# sequenceGameRev1-0.net
KiCad netlist of a schematic drawn in EAGLE
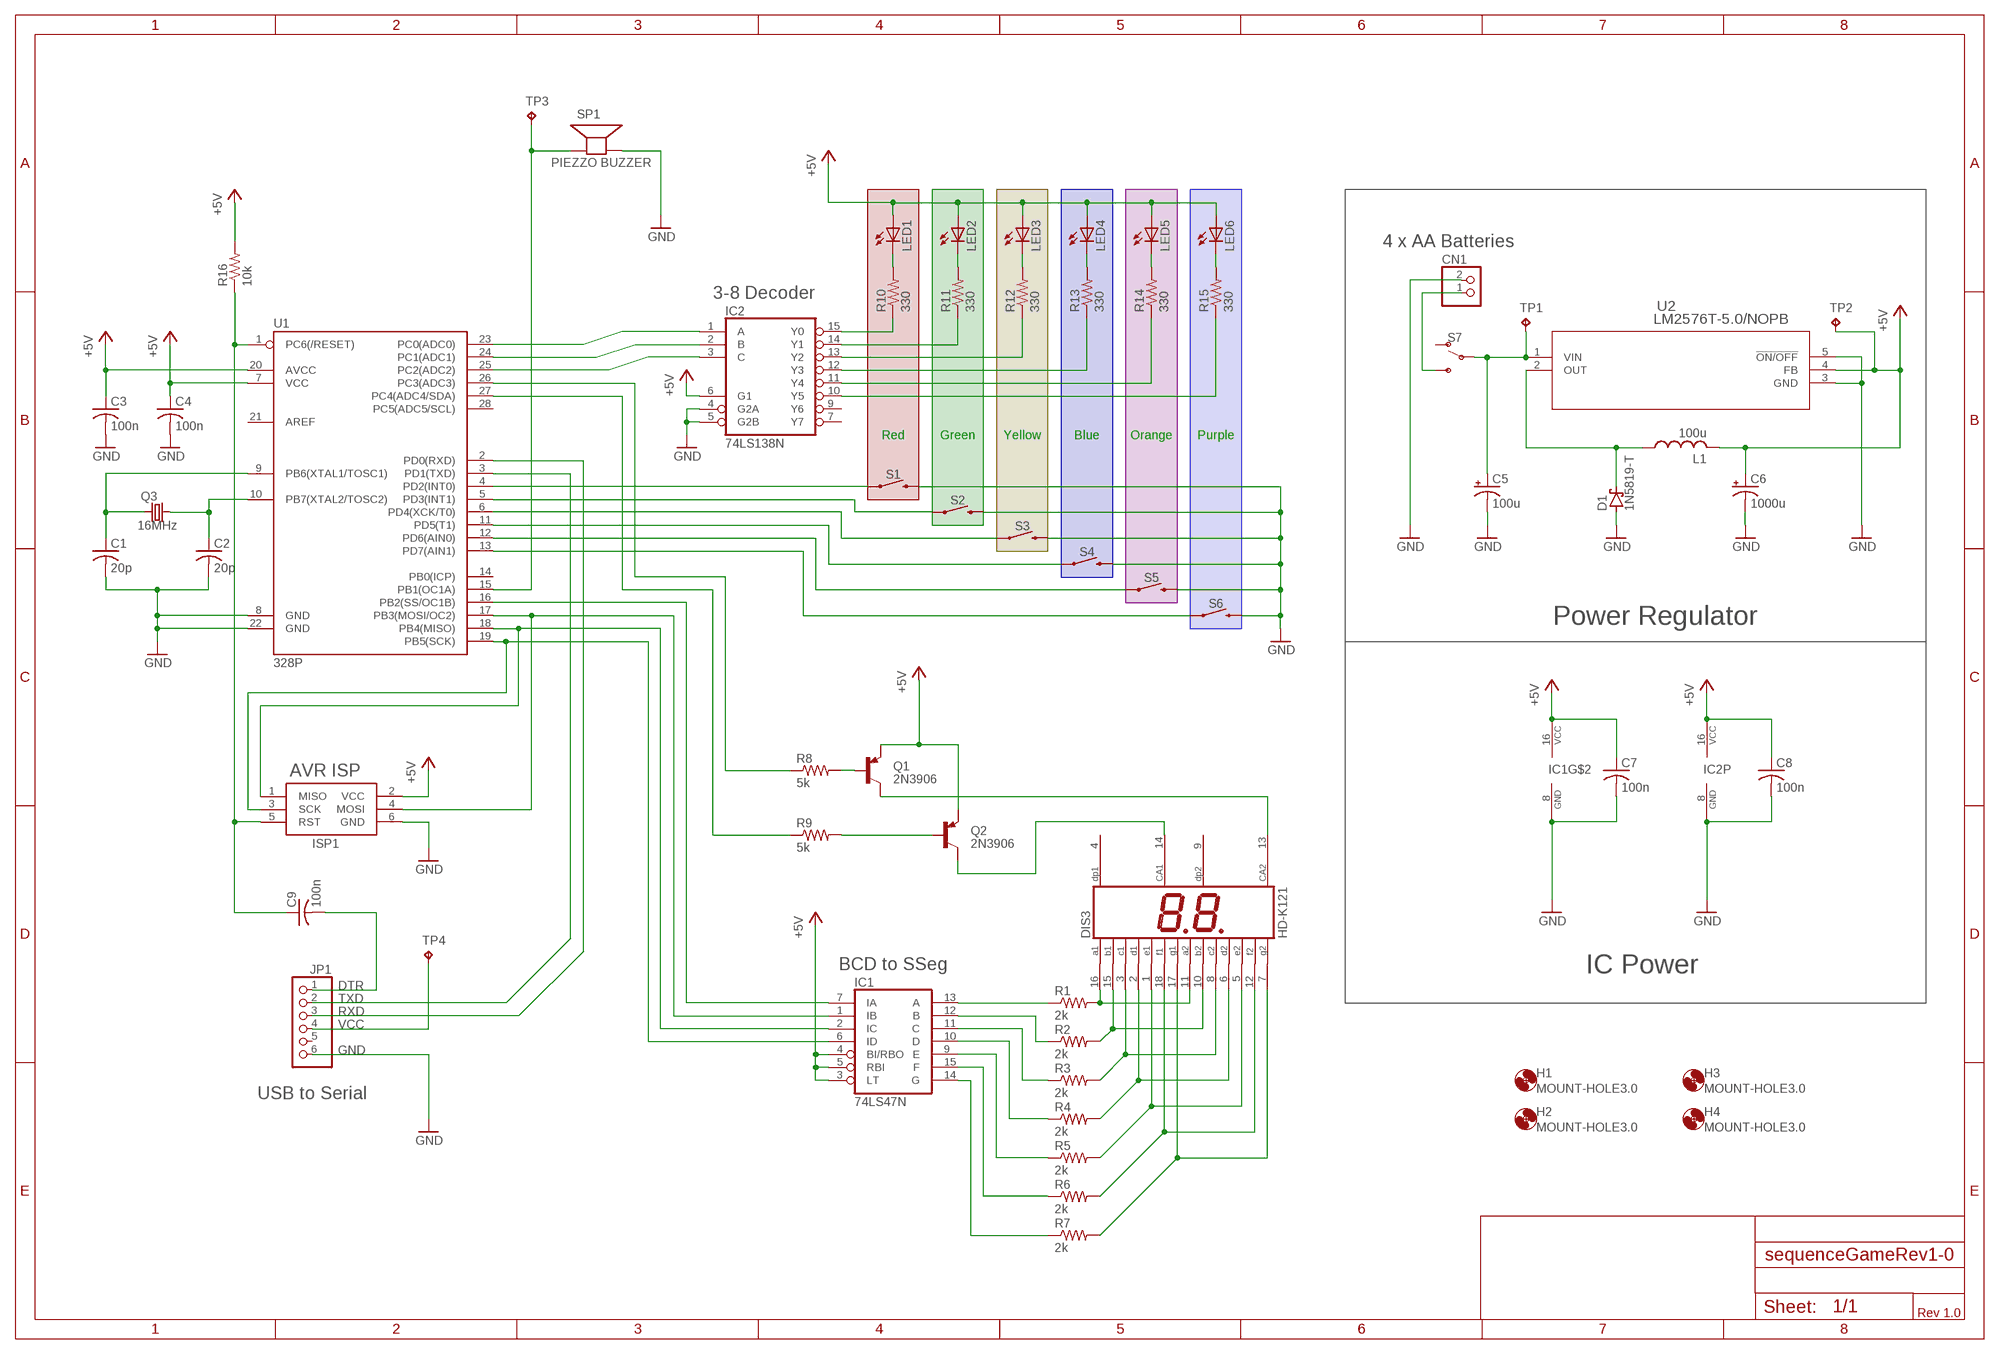
[diagram p0: schematic, sheet 1]

(export (version "E")
  (design (tool "Eeschema 10.0.6"))
  (components
    (comp (ref "C1")
      (value "20p")
      (footprint "eagle-import:C050-025X075")
      (libsource (lib "eagle-import") (part "C-US050-025X075"))
    )
    (comp (ref "C2")
      (value "20p")
      (footprint "eagle-import:C050-025X075")
      (libsource (lib "eagle-import") (part "C-US050-025X075"))
    )
    (comp (ref "C3")
      (value "100n")
      (footprint "eagle-import:C050-025X075")
      (libsource (lib "eagle-import") (part "C-US050-025X075"))
    )
    (comp (ref "C4")
      (value "100n")
      (footprint "eagle-import:C050-025X075")
      (libsource (lib "eagle-import") (part "C-US050-025X075"))
    )
    (comp (ref "C5")
      (value "100u")
      (footprint "eagle-import:E2,5-5")
      (libsource (lib "eagle-import") (part "CPOL-USE2.5-5"))
    )
    (comp (ref "C6")
      (value "1000u")
      (footprint "eagle-import:E5-10,5")
      (libsource (lib "eagle-import") (part "CPOL-USE5-10.5"))
    )
    (comp (ref "C7")
      (value "100n")
      (footprint "eagle-import:C050-025X075")
      (libsource (lib "eagle-import") (part "C-US050-025X075"))
    )
    (comp (ref "C8")
      (value "100n")
      (footprint "eagle-import:C050-025X075")
      (libsource (lib "eagle-import") (part "C-US050-025X075"))
    )
    (comp (ref "C9")
      (value "100n")
      (footprint "eagle-import:C050-025X075")
      (libsource (lib "eagle-import") (part "C-US050-025X075"))
    )
    (comp (ref "CN1")
      (value "JST_2PIN-THM")
      (footprint "eagle-import:JST-PH-2-THM")
      (libsource (lib "eagle-import") (part "JST_2PIN-THM"))
    )
    (comp (ref "D1")
      (value "1N5819-T")
      (footprint "eagle-import:DO41-7.6")
      (libsource (lib "eagle-import") (part "1N5819-T"))
    )
    (comp (ref "DIS3")
      (value "HD-K121")
      (footprint "eagle-import:HDSP-R")
      (libsource (lib "eagle-import") (part "HD-K121"))
    )
    (comp (ref "H1")
      (value "MOUNT-HOLE3.0")
      (footprint "eagle-import:3,0")
      (libsource (lib "eagle-import") (part "MOUNT-HOLE3.0"))
    )
    (comp (ref "H2")
      (value "MOUNT-HOLE3.0")
      (footprint "eagle-import:3,0")
      (libsource (lib "eagle-import") (part "MOUNT-HOLE3.0"))
    )
    (comp (ref "H3")
      (value "MOUNT-HOLE3.0")
      (footprint "eagle-import:3,0")
      (libsource (lib "eagle-import") (part "MOUNT-HOLE3.0"))
    )
    (comp (ref "H4")
      (value "MOUNT-HOLE3.0")
      (footprint "eagle-import:3,0")
      (libsource (lib "eagle-import") (part "MOUNT-HOLE3.0"))
    )
    (comp (ref "IC1")
      (value "74LS47N")
      (footprint "eagle-import:DIL16")
      (libsource (lib "eagle-import") (part "7447NLS"))
    )
    (comp (ref "IC2")
      (value "74LS138N")
      (footprint "eagle-import:DIL16")
      (libsource (lib "eagle-import") (part "74138NLS"))
    )
    (comp (ref "ISP1")
      (value "AVRISP-6")
      (footprint "eagle-import:AVRISP")
      (libsource (lib "eagle-import") (part "AVRISP-6"))
    )
    (comp (ref "JP1")
      (value "PINHD-1X6")
      (footprint "eagle-import:1X06")
      (libsource (lib "eagle-import") (part "PINHD-1X6"))
    )
    (comp (ref "L1")
      (value "100u")
      (footprint "eagle-import:0207_10")
      (libsource (lib "eagle-import") (part "L-US0207/10"))
    )
    (comp (ref "LED1")
      (value "LED5MM")
      (footprint "eagle-import:LED5MM")
      (libsource (lib "eagle-import") (part "LED5MM"))
    )
    (comp (ref "LED2")
      (value "LED5MM")
      (footprint "eagle-import:LED5MM")
      (libsource (lib "eagle-import") (part "LED5MM"))
    )
    (comp (ref "LED3")
      (value "LED5MM")
      (footprint "eagle-import:LED5MM")
      (libsource (lib "eagle-import") (part "LED5MM"))
    )
    (comp (ref "LED4")
      (value "LED5MM")
      (footprint "eagle-import:LED5MM")
      (libsource (lib "eagle-import") (part "LED5MM"))
    )
    (comp (ref "LED5")
      (value "LED5MM")
      (footprint "eagle-import:LED5MM")
      (libsource (lib "eagle-import") (part "LED5MM"))
    )
    (comp (ref "LED6")
      (value "LED5MM")
      (footprint "eagle-import:LED5MM")
      (libsource (lib "eagle-import") (part "LED5MM"))
    )
    (comp (ref "Q1")
      (value "2N3906")
      (footprint "eagle-import:TO92")
      (libsource (lib "eagle-import") (part "2N3906"))
    )
    (comp (ref "Q2")
      (value "2N3906")
      (footprint "eagle-import:TO92")
      (libsource (lib "eagle-import") (part "2N3906"))
    )
    (comp (ref "Q3")
      (value "16MHz")
      (footprint "eagle-import:HC49_S")
      (libsource (lib "eagle-import") (part "CRYSTALHC49S"))
    )
    (comp (ref "R1")
      (value "2k")
      (footprint "eagle-import:0207_10")
      (libsource (lib "eagle-import") (part "R-US_0207/10"))
    )
    (comp (ref "R2")
      (value "2k")
      (footprint "eagle-import:0207_10")
      (libsource (lib "eagle-import") (part "R-US_0207/10"))
    )
    (comp (ref "R3")
      (value "2k")
      (footprint "eagle-import:0207_10")
      (libsource (lib "eagle-import") (part "R-US_0207/10"))
    )
    (comp (ref "R4")
      (value "2k")
      (footprint "eagle-import:0207_10")
      (libsource (lib "eagle-import") (part "R-US_0207/10"))
    )
    (comp (ref "R5")
      (value "2k")
      (footprint "eagle-import:0207_10")
      (libsource (lib "eagle-import") (part "R-US_0207/10"))
    )
    (comp (ref "R6")
      (value "2k")
      (footprint "eagle-import:0207_10")
      (libsource (lib "eagle-import") (part "R-US_0207/10"))
    )
    (comp (ref "R7")
      (value "2k")
      (footprint "eagle-import:0207_10")
      (libsource (lib "eagle-import") (part "R-US_0207/10"))
    )
    (comp (ref "R8")
      (value "5k")
      (footprint "eagle-import:0207_10")
      (libsource (lib "eagle-import") (part "R-US_0207/10"))
    )
    (comp (ref "R9")
      (value "5k")
      (footprint "eagle-import:0207_10")
      (libsource (lib "eagle-import") (part "R-US_0207/10"))
    )
    (comp (ref "R10")
      (value "330")
      (footprint "eagle-import:0207_10")
      (libsource (lib "eagle-import") (part "R-US_0207/10"))
    )
    (comp (ref "R11")
      (value "330")
      (footprint "eagle-import:0207_10")
      (libsource (lib "eagle-import") (part "R-US_0207/10"))
    )
    (comp (ref "R12")
      (value "330")
      (footprint "eagle-import:0207_10")
      (libsource (lib "eagle-import") (part "R-US_0207/10"))
    )
    (comp (ref "R13")
      (value "330")
      (footprint "eagle-import:0207_10")
      (libsource (lib "eagle-import") (part "R-US_0207/10"))
    )
    (comp (ref "R14")
      (value "330")
      (footprint "eagle-import:0207_10")
      (libsource (lib "eagle-import") (part "R-US_0207/10"))
    )
    (comp (ref "R15")
      (value "330")
      (footprint "eagle-import:0207_10")
      (libsource (lib "eagle-import") (part "R-US_0207/10"))
    )
    (comp (ref "R16")
      (value "10k")
      (footprint "eagle-import:0207_10")
      (libsource (lib "eagle-import") (part "R-US_0207/10"))
    )
    (comp (ref "S1")
      (value "MOMENTARY-SWITCH-SPST-PTH-6.0MM")
      (footprint "eagle-import:TACTILE_SWITCH_PTH_6.0MM")
      (libsource (lib "eagle-import") (part "MOMENTARY-SWITCH-SPST-PTH-6.0MM"))
    )
    (comp (ref "S2")
      (value "MOMENTARY-SWITCH-SPST-PTH-6.0MM")
      (footprint "eagle-import:TACTILE_SWITCH_PTH_6.0MM")
      (libsource (lib "eagle-import") (part "MOMENTARY-SWITCH-SPST-PTH-6.0MM"))
    )
    (comp (ref "S3")
      (value "MOMENTARY-SWITCH-SPST-PTH-6.0MM")
      (footprint "eagle-import:TACTILE_SWITCH_PTH_6.0MM")
      (libsource (lib "eagle-import") (part "MOMENTARY-SWITCH-SPST-PTH-6.0MM"))
    )
    (comp (ref "S4")
      (value "MOMENTARY-SWITCH-SPST-PTH-6.0MM")
      (footprint "eagle-import:TACTILE_SWITCH_PTH_6.0MM")
      (libsource (lib "eagle-import") (part "MOMENTARY-SWITCH-SPST-PTH-6.0MM"))
    )
    (comp (ref "S5")
      (value "MOMENTARY-SWITCH-SPST-PTH-6.0MM")
      (footprint "eagle-import:TACTILE_SWITCH_PTH_6.0MM")
      (libsource (lib "eagle-import") (part "MOMENTARY-SWITCH-SPST-PTH-6.0MM"))
    )
    (comp (ref "S6")
      (value "MOMENTARY-SWITCH-SPST-PTH-6.0MM")
      (footprint "eagle-import:TACTILE_SWITCH_PTH_6.0MM")
      (libsource (lib "eagle-import") (part "MOMENTARY-SWITCH-SPST-PTH-6.0MM"))
    )
    (comp (ref "S7")
      (value "SWITCH-SPDT-PTH-11.6X4.0MM")
      (footprint "eagle-import:SWITCH_SPDT_PTH_11.6X4.0MM")
      (libsource (lib "eagle-import") (part "SWITCH-SPDT-PTH-11.6X4.0MM"))
    )
    (comp (ref "SP1")
      (value "PIEZZO BUZZER")
      (footprint "eagle-import:AL60P")
      (libsource (lib "eagle-import") (part "SPEAKER/AL60P"))
    )
    (comp (ref "TP1")
      (value "TPB1,27")
      (footprint "eagle-import:B1,27")
      (libsource (lib "eagle-import") (part "TPB1,27"))
    )
    (comp (ref "TP2")
      (value "TPB1,27")
      (footprint "eagle-import:B1,27")
      (libsource (lib "eagle-import") (part "TPB1,27"))
    )
    (comp (ref "TP3")
      (value "TPB1,27")
      (footprint "eagle-import:B1,27")
      (libsource (lib "eagle-import") (part "TPB1,27"))
    )
    (comp (ref "TP4")
      (value "TPB1,27")
      (footprint "eagle-import:B1,27")
      (libsource (lib "eagle-import") (part "TPB1,27"))
    )
    (comp (ref "U1")
      (value "328P")
      (footprint "eagle-import:DIP28")
      (libsource (lib "eagle-import") (part "ATMEGA328P_PDIP"))
    )
    (comp (ref "U2")
      (value "LM2576T-5.0/NOPB")
      (footprint "eagle-import:T05A_TEX")
      (fields (field (name "COPYRIGHT") "Copyright (C) 2018 Accelerated Designs. All rights reserved"))
      (libsource (lib "eagle-import") (part "LM2576T-5.0/NOPB"))
    )
  )
  (nets
    (net (code "1") (name "+5V") (class "Default")
      (node (ref "C3") (pin "1") (pinfunction "1_1") (pintype "passive"))
      (node (ref "C4") (pin "1") (pinfunction "1_1") (pintype "passive"))
      (node (ref "C6") (pin "+") (pinfunction "+_+") (pintype "passive"))
      (node (ref "C7") (pin "1") (pinfunction "1_1") (pintype "passive"))
      (node (ref "C8") (pin "1") (pinfunction "1_1") (pintype "passive"))
      (node (ref "IC1") (pin "16") (pinfunction "VCC_16") (pintype "power_in"))
      (node (ref "IC1") (pin "3") (pinfunction "LT_3") (pintype "input"))
      (node (ref "IC1") (pin "4") (pinfunction "BI/RBO_4") (pintype "input"))
      (node (ref "IC1") (pin "5") (pinfunction "RBI_5") (pintype "input"))
      (node (ref "IC2") (pin "16") (pinfunction "VCC_16") (pintype "power_in"))
      (node (ref "IC2") (pin "6") (pinfunction "G1_6") (pintype "input"))
      (node (ref "ISP1") (pin "2") (pinfunction "VCC_2") (pintype "power_in"))
      (node (ref "L1") (pin "2") (pinfunction "2_2") (pintype "passive"))
      (node (ref "LED1") (pin "A") (pinfunction "A_A") (pintype "passive"))
      (node (ref "LED2") (pin "A") (pinfunction "A_A") (pintype "passive"))
      (node (ref "LED3") (pin "A") (pinfunction "A_A") (pintype "passive"))
      (node (ref "LED4") (pin "A") (pinfunction "A_A") (pintype "passive"))
      (node (ref "LED5") (pin "A") (pinfunction "A_A") (pintype "passive"))
      (node (ref "LED6") (pin "A") (pinfunction "A_A") (pintype "passive"))
      (node (ref "Q1") (pin "3") (pinfunction "E_3") (pintype "passive"))
      (node (ref "Q2") (pin "3") (pinfunction "E_3") (pintype "passive"))
      (node (ref "R16") (pin "2") (pinfunction "2_2") (pintype "passive"))
      (node (ref "TP2") (pin "TP") (pinfunction "TP_TP") (pintype "input"))
      (node (ref "U1") (pin "20") (pinfunction "AVCC_20") (pintype "bidirectional"))
      (node (ref "U1") (pin "7") (pinfunction "VCC_7") (pintype "bidirectional"))
      (node (ref "U2") (pin "4") (pinfunction "FB_4") (pintype "input"))
    )
    (net (code "2") (name "/DTR") (class "Default")
      (node (ref "C9") (pin "2") (pinfunction "2_2") (pintype "passive"))
      (node (ref "JP1") (pin "1") (pinfunction "1_1") (pintype "passive"))
    )
    (net (code "3") (name "/RXD") (class "Default")
      (node (ref "JP1") (pin "3") (pinfunction "3_3") (pintype "passive"))
      (node (ref "U1") (pin "2") (pinfunction "PD0(RXD)_2") (pintype "bidirectional"))
    )
    (net (code "4") (name "/TXD") (class "Default")
      (node (ref "JP1") (pin "2") (pinfunction "2_2") (pintype "passive"))
      (node (ref "U1") (pin "3") (pinfunction "PD1(TXD)_3") (pintype "bidirectional"))
    )
    (net (code "5") (name "/VCC") (class "Default")
      (node (ref "JP1") (pin "4") (pinfunction "4_4") (pintype "passive"))
      (node (ref "TP4") (pin "TP") (pinfunction "TP_TP") (pintype "input"))
    )
    (net (code "6") (name "GND") (class "Default")
      (node (ref "C1") (pin "2") (pinfunction "2_2") (pintype "passive"))
      (node (ref "C2") (pin "2") (pinfunction "2_2") (pintype "passive"))
      (node (ref "C3") (pin "2") (pinfunction "2_2") (pintype "passive"))
      (node (ref "C4") (pin "2") (pinfunction "2_2") (pintype "passive"))
      (node (ref "C5") (pin "-") (pinfunction "-_-") (pintype "passive"))
      (node (ref "C6") (pin "-") (pinfunction "-_-") (pintype "passive"))
      (node (ref "C7") (pin "2") (pinfunction "2_2") (pintype "passive"))
      (node (ref "C8") (pin "2") (pinfunction "2_2") (pintype "passive"))
      (node (ref "CN1") (pin "2") (pinfunction "1_2") (pintype "passive"))
      (node (ref "D1") (pin "A") (pinfunction "A_A") (pintype "passive"))
      (node (ref "IC1") (pin "8") (pinfunction "GND_8") (pintype "power_in"))
      (node (ref "IC2") (pin "4") (pinfunction "G2A_4") (pintype "input"))
      (node (ref "IC2") (pin "5") (pinfunction "G2B_5") (pintype "input"))
      (node (ref "IC2") (pin "8") (pinfunction "GND_8") (pintype "power_in"))
      (node (ref "ISP1") (pin "6") (pinfunction "GND_6") (pintype "power_in"))
      (node (ref "JP1") (pin "6") (pinfunction "6_6") (pintype "passive"))
      (node (ref "S1") (pin "3") (pinfunction "2_3") (pintype "passive"))
      (node (ref "S2") (pin "3") (pinfunction "2_3") (pintype "passive"))
      (node (ref "S3") (pin "3") (pinfunction "2_3") (pintype "passive"))
      (node (ref "S4") (pin "3") (pinfunction "2_3") (pintype "passive"))
      (node (ref "S5") (pin "3") (pinfunction "2_3") (pintype "passive"))
      (node (ref "S6") (pin "3") (pinfunction "2_3") (pintype "passive"))
      (node (ref "SP1") (pin "2") (pinfunction "-_2") (pintype "passive"))
      (node (ref "U1") (pin "22") (pinfunction "GND_22") (pintype "bidirectional"))
      (node (ref "U1") (pin "8") (pinfunction "GND_8") (pintype "bidirectional"))
      (node (ref "U2") (pin "3") (pinfunction "GND_3") (pintype "power_in"))
      (node (ref "U2") (pin "5") (pinfunction "~{ON/OFF}_5") (pintype "input"))
    )
    (net (code "7") (name "Net-(CN1-2)") (class "Default")
      (node (ref "CN1") (pin "1") (pinfunction "2_1") (pintype "passive"))
      (node (ref "S7") (pin "3") (pinfunction "S_3") (pintype "passive"))
    )
    (net (code "8") (name "Net-(DIS3-A1)") (class "Default")
      (node (ref "DIS3") (pin "11") (pinfunction "A2_11") (pintype "passive"))
      (node (ref "DIS3") (pin "16") (pinfunction "A1_16") (pintype "passive"))
      (node (ref "R1") (pin "2") (pinfunction "2_2") (pintype "passive"))
    )
    (net (code "9") (name "Net-(DIS3-B1)") (class "Default")
      (node (ref "DIS3") (pin "10") (pinfunction "B2_10") (pintype "passive"))
      (node (ref "DIS3") (pin "15") (pinfunction "B1_15") (pintype "passive"))
      (node (ref "R2") (pin "2") (pinfunction "2_2") (pintype "passive"))
    )
    (net (code "10") (name "Net-(DIS3-C1)") (class "Default")
      (node (ref "DIS3") (pin "3") (pinfunction "C1_3") (pintype "passive"))
      (node (ref "DIS3") (pin "8") (pinfunction "C2_8") (pintype "passive"))
      (node (ref "R3") (pin "2") (pinfunction "2_2") (pintype "passive"))
    )
    (net (code "11") (name "Net-(DIS3-CA1)") (class "Default")
      (node (ref "DIS3") (pin "14") (pinfunction "CA1_14") (pintype "passive"))
      (node (ref "Q2") (pin "1") (pinfunction "C_1") (pintype "passive"))
    )
    (net (code "12") (name "Net-(DIS3-CA2)") (class "Default")
      (node (ref "DIS3") (pin "13") (pinfunction "CA2_13") (pintype "passive"))
      (node (ref "Q1") (pin "1") (pinfunction "C_1") (pintype "passive"))
    )
    (net (code "13") (name "Net-(DIS3-D1)") (class "Default")
      (node (ref "DIS3") (pin "2") (pinfunction "D1_2") (pintype "passive"))
      (node (ref "DIS3") (pin "6") (pinfunction "D2_6") (pintype "passive"))
      (node (ref "R4") (pin "2") (pinfunction "2_2") (pintype "passive"))
    )
    (net (code "14") (name "Net-(DIS3-E1)") (class "Default")
      (node (ref "DIS3") (pin "1") (pinfunction "E1_1") (pintype "passive"))
      (node (ref "DIS3") (pin "5") (pinfunction "E2_5") (pintype "passive"))
      (node (ref "R5") (pin "2") (pinfunction "2_2") (pintype "passive"))
    )
    (net (code "15") (name "Net-(DIS3-F1)") (class "Default")
      (node (ref "DIS3") (pin "12") (pinfunction "F2_12") (pintype "passive"))
      (node (ref "DIS3") (pin "18") (pinfunction "F1_18") (pintype "passive"))
      (node (ref "R6") (pin "2") (pinfunction "2_2") (pintype "passive"))
    )
    (net (code "16") (name "Net-(DIS3-G1)") (class "Default")
      (node (ref "DIS3") (pin "17") (pinfunction "G1_17") (pintype "passive"))
      (node (ref "DIS3") (pin "7") (pinfunction "G2_7") (pintype "passive"))
      (node (ref "R7") (pin "2") (pinfunction "2_2") (pintype "passive"))
    )
    (net (code "17") (name "Net-(IC1A-A)") (class "Default")
      (node (ref "IC1") (pin "13") (pinfunction "A_13") (pintype "output"))
      (node (ref "R1") (pin "1") (pinfunction "1_1") (pintype "passive"))
    )
    (net (code "18") (name "Net-(IC1A-B)") (class "Default")
      (node (ref "IC1") (pin "12") (pinfunction "B_12") (pintype "output"))
      (node (ref "R2") (pin "1") (pinfunction "1_1") (pintype "passive"))
    )
    (net (code "19") (name "Net-(IC1A-C)") (class "Default")
      (node (ref "IC1") (pin "11") (pinfunction "C_11") (pintype "output"))
      (node (ref "R3") (pin "1") (pinfunction "1_1") (pintype "passive"))
    )
    (net (code "20") (name "Net-(IC1A-D)") (class "Default")
      (node (ref "IC1") (pin "10") (pinfunction "D_10") (pintype "output"))
      (node (ref "R4") (pin "1") (pinfunction "1_1") (pintype "passive"))
    )
    (net (code "21") (name "Net-(IC1A-E)") (class "Default")
      (node (ref "IC1") (pin "9") (pinfunction "E_9") (pintype "output"))
      (node (ref "R5") (pin "1") (pinfunction "1_1") (pintype "passive"))
    )
    (net (code "22") (name "Net-(IC1A-F)") (class "Default")
      (node (ref "IC1") (pin "15") (pinfunction "F_15") (pintype "output"))
      (node (ref "R6") (pin "1") (pinfunction "1_1") (pintype "passive"))
    )
    (net (code "23") (name "Net-(IC1A-G)") (class "Default")
      (node (ref "IC1") (pin "14") (pinfunction "G_14") (pintype "output"))
      (node (ref "R7") (pin "1") (pinfunction "1_1") (pintype "passive"))
    )
    (net (code "24") (name "Net-(IC1A-IA)") (class "Default")
      (node (ref "IC1") (pin "7") (pinfunction "IA_7") (pintype "input"))
      (node (ref "U1") (pin "16") (pinfunction "PB2(SS/OC1B)_16") (pintype "bidirectional"))
    )
    (net (code "25") (name "Net-(IC1A-IB)") (class "Default")
      (node (ref "IC1") (pin "1") (pinfunction "IB_1") (pintype "input"))
      (node (ref "ISP1") (pin "4") (pinfunction "MOSI_4") (pintype "output"))
      (node (ref "U1") (pin "17") (pinfunction "PB3(MOSI/OC2)_17") (pintype "bidirectional"))
    )
    (net (code "26") (name "Net-(IC1A-IC)") (class "Default")
      (node (ref "IC1") (pin "2") (pinfunction "IC_2") (pintype "input"))
      (node (ref "ISP1") (pin "1") (pinfunction "MISO_1") (pintype "input"))
      (node (ref "U1") (pin "18") (pinfunction "PB4(MISO)_18") (pintype "bidirectional"))
    )
    (net (code "27") (name "Net-(IC1A-ID)") (class "Default")
      (node (ref "IC1") (pin "6") (pinfunction "ID_6") (pintype "input"))
      (node (ref "ISP1") (pin "3") (pinfunction "SCK_3") (pintype "output"))
      (node (ref "U1") (pin "19") (pinfunction "PB5(SCK)_19") (pintype "bidirectional"))
    )
    (net (code "28") (name "Net-(IC2A-A)") (class "Default")
      (node (ref "IC2") (pin "1") (pinfunction "A_1") (pintype "input"))
      (node (ref "U1") (pin "23") (pinfunction "PC0(ADC0)_23") (pintype "bidirectional"))
    )
    (net (code "29") (name "Net-(IC2A-B)") (class "Default")
      (node (ref "IC2") (pin "2") (pinfunction "B_2") (pintype "input"))
      (node (ref "U1") (pin "24") (pinfunction "PC1(ADC1)_24") (pintype "bidirectional"))
    )
    (net (code "30") (name "Net-(IC2A-C)") (class "Default")
      (node (ref "IC2") (pin "3") (pinfunction "C_3") (pintype "input"))
      (node (ref "U1") (pin "25") (pinfunction "PC2(ADC2)_25") (pintype "bidirectional"))
    )
    (net (code "31") (name "Net-(IC2A-Y0)") (class "Default")
      (node (ref "IC2") (pin "15") (pinfunction "Y0_15") (pintype "output"))
      (node (ref "R10") (pin "1") (pinfunction "1_1") (pintype "passive"))
    )
    (net (code "32") (name "Net-(IC2A-Y1)") (class "Default")
      (node (ref "IC2") (pin "14") (pinfunction "Y1_14") (pintype "output"))
      (node (ref "R11") (pin "1") (pinfunction "1_1") (pintype "passive"))
    )
    (net (code "33") (name "Net-(IC2A-Y2)") (class "Default")
      (node (ref "IC2") (pin "13") (pinfunction "Y2_13") (pintype "output"))
      (node (ref "R12") (pin "1") (pinfunction "1_1") (pintype "passive"))
    )
    (net (code "34") (name "Net-(IC2A-Y3)") (class "Default")
      (node (ref "IC2") (pin "12") (pinfunction "Y3_12") (pintype "output"))
      (node (ref "R13") (pin "1") (pinfunction "1_1") (pintype "passive"))
    )
    (net (code "35") (name "Net-(IC2A-Y4)") (class "Default")
      (node (ref "IC2") (pin "11") (pinfunction "Y4_11") (pintype "output"))
      (node (ref "R14") (pin "1") (pinfunction "1_1") (pintype "passive"))
    )
    (net (code "36") (name "Net-(IC2A-Y5)") (class "Default")
      (node (ref "IC2") (pin "10") (pinfunction "Y5_10") (pintype "output"))
      (node (ref "R15") (pin "1") (pinfunction "1_1") (pintype "passive"))
    )
    (net (code "37") (name "Net-(ISP1-RST)") (class "Default")
      (node (ref "C9") (pin "1") (pinfunction "1_1") (pintype "passive"))
      (node (ref "ISP1") (pin "5") (pinfunction "RST_5") (pintype "output"))
      (node (ref "R16") (pin "1") (pinfunction "1_1") (pintype "passive"))
      (node (ref "U1") (pin "1") (pinfunction "PC6(/RESET)_1") (pintype "bidirectional"))
    )
    (net (code "38") (name "Net-(LED1-C)") (class "Default")
      (node (ref "LED1") (pin "K") (pinfunction "C_K") (pintype "passive"))
      (node (ref "R10") (pin "2") (pinfunction "2_2") (pintype "passive"))
    )
    (net (code "39") (name "Net-(LED2-C)") (class "Default")
      (node (ref "LED2") (pin "K") (pinfunction "C_K") (pintype "passive"))
      (node (ref "R11") (pin "2") (pinfunction "2_2") (pintype "passive"))
    )
    (net (code "40") (name "Net-(LED3-C)") (class "Default")
      (node (ref "LED3") (pin "K") (pinfunction "C_K") (pintype "passive"))
      (node (ref "R12") (pin "2") (pinfunction "2_2") (pintype "passive"))
    )
    (net (code "41") (name "Net-(LED4-C)") (class "Default")
      (node (ref "LED4") (pin "K") (pinfunction "C_K") (pintype "passive"))
      (node (ref "R13") (pin "2") (pinfunction "2_2") (pintype "passive"))
    )
    (net (code "42") (name "Net-(LED5-C)") (class "Default")
      (node (ref "LED5") (pin "K") (pinfunction "C_K") (pintype "passive"))
      (node (ref "R14") (pin "2") (pinfunction "2_2") (pintype "passive"))
    )
    (net (code "43") (name "Net-(LED6-C)") (class "Default")
      (node (ref "LED6") (pin "K") (pinfunction "C_K") (pintype "passive"))
      (node (ref "R15") (pin "2") (pinfunction "2_2") (pintype "passive"))
    )
    (net (code "44") (name "Net-(Q1-B)") (class "Default")
      (node (ref "Q1") (pin "2") (pinfunction "B_2") (pintype "passive"))
      (node (ref "R8") (pin "2") (pinfunction "2_2") (pintype "passive"))
    )
    (net (code "45") (name "Net-(Q2-B)") (class "Default")
      (node (ref "Q2") (pin "2") (pinfunction "B_2") (pintype "passive"))
      (node (ref "R9") (pin "2") (pinfunction "2_2") (pintype "passive"))
    )
    (net (code "46") (name "Net-(S7-P)") (class "Default")
      (node (ref "C5") (pin "+") (pinfunction "+_+") (pintype "passive"))
      (node (ref "S7") (pin "2") (pinfunction "P_2") (pintype "passive"))
      (node (ref "TP1") (pin "TP") (pinfunction "TP_TP") (pintype "input"))
      (node (ref "U2") (pin "1") (pinfunction "VIN_1") (pintype "power_in"))
    )
    (net (code "47") (name "Net-(SP1-+)") (class "Default")
      (node (ref "SP1") (pin "1") (pinfunction "+_1") (pintype "passive"))
      (node (ref "TP3") (pin "TP") (pinfunction "TP_TP") (pintype "input"))
      (node (ref "U1") (pin "15") (pinfunction "PB1(OC1A)_15") (pintype "bidirectional"))
    )
    (net (code "48") (name "Net-(U1-PB6(XTAL1{slash}TOSC1))") (class "Default")
      (node (ref "C1") (pin "1") (pinfunction "1_1") (pintype "passive"))
      (node (ref "Q3") (pin "2") (pinfunction "2_2") (pintype "passive"))
      (node (ref "U1") (pin "9") (pinfunction "PB6(XTAL1/TOSC1)_9") (pintype "bidirectional"))
    )
    (net (code "49") (name "Net-(U1-PB7(XTAL2{slash}TOSC2))") (class "Default")
      (node (ref "C2") (pin "1") (pinfunction "1_1") (pintype "passive"))
      (node (ref "Q3") (pin "1") (pinfunction "1_1") (pintype "passive"))
      (node (ref "U1") (pin "10") (pinfunction "PB7(XTAL2/TOSC2)_10") (pintype "bidirectional"))
    )
    (net (code "50") (name "Net-(U1-PC3(ADC3))") (class "Default")
      (node (ref "R8") (pin "1") (pinfunction "1_1") (pintype "passive"))
      (node (ref "U1") (pin "26") (pinfunction "PC3(ADC3)_26") (pintype "bidirectional"))
    )
    (net (code "51") (name "Net-(U1-PC4(ADC4{slash}SDA))") (class "Default")
      (node (ref "R9") (pin "1") (pinfunction "1_1") (pintype "passive"))
      (node (ref "U1") (pin "27") (pinfunction "PC4(ADC4/SDA)_27") (pintype "bidirectional"))
    )
    (net (code "52") (name "Net-(U1-PD2(INT0))") (class "Default")
      (node (ref "S1") (pin "1") (pinfunction "1_1") (pintype "passive"))
      (node (ref "U1") (pin "4") (pinfunction "PD2(INT0)_4") (pintype "bidirectional"))
    )
    (net (code "53") (name "Net-(U1-PD3(INT1))") (class "Default")
      (node (ref "S2") (pin "1") (pinfunction "1_1") (pintype "passive"))
      (node (ref "U1") (pin "5") (pinfunction "PD3(INT1)_5") (pintype "bidirectional"))
    )
    (net (code "54") (name "Net-(U1-PD4(XCK{slash}T0))") (class "Default")
      (node (ref "S3") (pin "1") (pinfunction "1_1") (pintype "passive"))
      (node (ref "U1") (pin "6") (pinfunction "PD4(XCK/T0)_6") (pintype "bidirectional"))
    )
    (net (code "55") (name "Net-(U1-PD5(T1))") (class "Default")
      (node (ref "S4") (pin "1") (pinfunction "1_1") (pintype "passive"))
      (node (ref "U1") (pin "11") (pinfunction "PD5(T1)_11") (pintype "bidirectional"))
    )
    (net (code "56") (name "Net-(U1-PD6(AIN0))") (class "Default")
      (node (ref "S5") (pin "1") (pinfunction "1_1") (pintype "passive"))
      (node (ref "U1") (pin "12") (pinfunction "PD6(AIN0)_12") (pintype "bidirectional"))
    )
    (net (code "57") (name "Net-(U1-PD7(AIN1))") (class "Default")
      (node (ref "S6") (pin "1") (pinfunction "1_1") (pintype "passive"))
      (node (ref "U1") (pin "13") (pinfunction "PD7(AIN1)_13") (pintype "bidirectional"))
    )
    (net (code "58") (name "Net-(U2-OUT)") (class "Default")
      (node (ref "D1") (pin "C") (pinfunction "C_C") (pintype "passive"))
      (node (ref "L1") (pin "1") (pinfunction "1_1") (pintype "passive"))
      (node (ref "U2") (pin "2") (pinfunction "OUT_2") (pintype "power_in"))
    )
    (net (code "59") (name "unconnected-(DIS3-DP1-Pad4)") (class "Default")
      (node (ref "DIS3") (pin "4") (pinfunction "DP1_4") (pintype "passive"))
    )
    (net (code "60") (name "unconnected-(DIS3-DP2-Pad9)") (class "Default")
      (node (ref "DIS3") (pin "9") (pinfunction "DP2_9") (pintype "passive"))
    )
    (net (code "61") (name "unconnected-(IC2A-Y6-Pad9)") (class "Default")
      (node (ref "IC2") (pin "9") (pinfunction "Y6_9") (pintype "output"))
    )
    (net (code "62") (name "unconnected-(IC2A-Y7-Pad7)") (class "Default")
      (node (ref "IC2") (pin "7") (pinfunction "Y7_7") (pintype "output"))
    )
    (net (code "63") (name "unconnected-(JP1-Pad5)") (class "Default")
      (node (ref "JP1") (pin "5") (pinfunction "5_5") (pintype "passive"))
    )
    (net (code "64") (name "unconnected-(S7-O-Pad1)") (class "Default")
      (node (ref "S7") (pin "1") (pinfunction "O_1") (pintype "passive"))
    )
    (net (code "65") (name "unconnected-(U1-AREF-Pad21)") (class "Default")
      (node (ref "U1") (pin "21") (pinfunction "AREF_21") (pintype "bidirectional"))
    )
    (net (code "66") (name "unconnected-(U1-PB0(ICP)-Pad14)") (class "Default")
      (node (ref "U1") (pin "14") (pinfunction "PB0(ICP)_14") (pintype "bidirectional"))
    )
    (net (code "67") (name "unconnected-(U1-PC5(ADC5{slash}SCL)-Pad28)") (class "Default")
      (node (ref "U1") (pin "28") (pinfunction "PC5(ADC5/SCL)_28") (pintype "bidirectional"))
    )
  )
)
